# Audio.net
KiCad netlist of a schematic drawn in Altium Designer
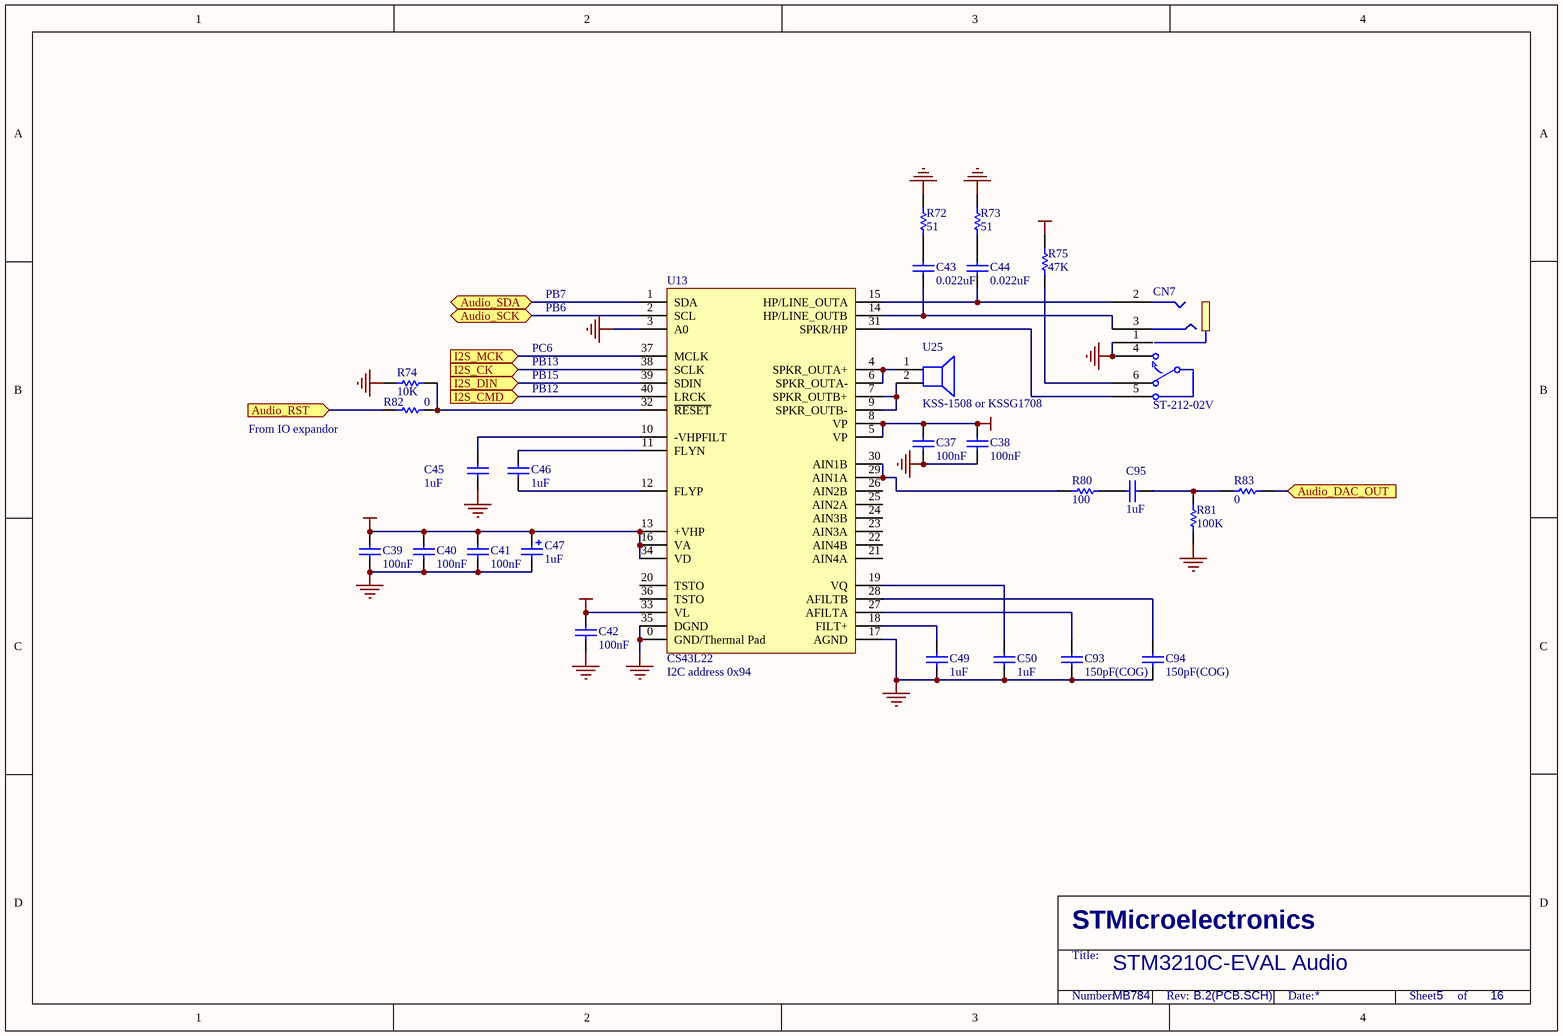
[diagram p0: Audio.SchDoc]

(export (version "E")
  (design (tool "Eeschema 10.0.6"))
  (components
    (comp (ref "C37")
      (value "100nF")
      (footprint "0603C")
      (description "Capacitor")
      (fields (field (name "PUBLISHER") "Altium Limited"))
      (libsource (lib "Miscellaneous Devices") (part "CAP"))
    )
    (comp (ref "C38")
      (value "100nF")
      (footprint "0603C")
      (description "Capacitor")
      (fields (field (name "PUBLISHER") "Altium Limited"))
      (libsource (lib "Miscellaneous Devices") (part "CAP"))
    )
    (comp (ref "C39")
      (value "100nF")
      (footprint "0603C")
      (description "Capacitor")
      (fields (field (name "PUBLISHER") "Altium Limited"))
      (libsource (lib "Miscellaneous Devices") (part "CAP"))
    )
    (comp (ref "C40")
      (value "100nF")
      (footprint "0603C")
      (description "Capacitor")
      (fields (field (name "PUBLISHER") "Altium Limited"))
      (libsource (lib "Miscellaneous Devices") (part "CAP"))
    )
    (comp (ref "C41")
      (value "100nF")
      (footprint "0603C")
      (description "Capacitor")
      (fields (field (name "PUBLISHER") "Altium Limited"))
      (libsource (lib "Miscellaneous Devices") (part "CAP"))
    )
    (comp (ref "C42")
      (value "100nF")
      (footprint "0603C")
      (description "Capacitor")
      (fields (field (name "PUBLISHER") "Altium Limited"))
      (libsource (lib "Miscellaneous Devices") (part "CAP"))
    )
    (comp (ref "C43")
      (value "0.022uF")
      (footprint "0603C")
      (description "Capacitor")
      (fields (field (name "PUBLISHER") "Altium Limited"))
      (libsource (lib "Miscellaneous Devices") (part "CAP"))
    )
    (comp (ref "C44")
      (value "0.022uF")
      (footprint "0603C")
      (description "Capacitor")
      (fields (field (name "PUBLISHER") "Altium Limited"))
      (libsource (lib "Miscellaneous Devices") (part "CAP"))
    )
    (comp (ref "C45")
      (value "1uF")
      (footprint "0603C")
      (description "Capacitor")
      (fields (field (name "PUBLISHER") "Altium Limited"))
      (libsource (lib "Miscellaneous Devices") (part "CAP"))
    )
    (comp (ref "C46")
      (value "1uF")
      (footprint "0603C")
      (description "Capacitor")
      (fields (field (name "PUBLISHER") "Altium Limited"))
      (libsource (lib "Miscellaneous Devices") (part "CAP"))
    )
    (comp (ref "C47")
      (value "1uF")
      (footprint "TAN-A")
      (description "Polarized Capacitor (Radial)")
      (fields (field (name "PUBLISHER") "Altium Limited"))
      (libsource (lib "Miscellaneous Devices") (part "Cap Pol1"))
    )
    (comp (ref "C49")
      (value "1uF")
      (footprint "0603C")
      (description "Capacitor")
      (fields (field (name "PUBLISHER") "Altium Limited"))
      (libsource (lib "Miscellaneous Devices") (part "CAP"))
    )
    (comp (ref "C50")
      (value "1uF")
      (footprint "0603C")
      (description "Capacitor")
      (fields (field (name "PUBLISHER") "Altium Limited"))
      (libsource (lib "Miscellaneous Devices") (part "CAP"))
    )
    (comp (ref "C93")
      (value "150pF(COG)")
      (footprint "0603C")
      (description "Capacitor")
      (fields (field (name "PUBLISHER") "Altium Limited"))
      (libsource (lib "Miscellaneous Devices") (part "CAP"))
    )
    (comp (ref "C94")
      (value "150pF(COG)")
      (footprint "0603C")
      (description "Capacitor")
      (fields (field (name "PUBLISHER") "Altium Limited"))
      (libsource (lib "Miscellaneous Devices") (part "CAP"))
    )
    (comp (ref "C95")
      (value "1uF")
      (footprint "0603C")
      (description "Capacitor")
      (fields (field (name "PUBLISHER") "Altium Limited"))
      (libsource (lib "Miscellaneous Devices") (part "CAP"))
    )
    (comp (ref "CN7")
      (value "ST-212-02V")
      (footprint "ST-212-02V")
      (libsource (lib "MB784") (part "ST-212-02V"))
    )
    (comp (ref "R72")
      (value "51")
      (footprint "0603R")
      (description "Resistor")
      (fields (field (name "PUBLISHER") "Altium Limited"))
      (libsource (lib "Miscellaneous Devices") (part "res1"))
    )
    (comp (ref "R73")
      (value "51")
      (footprint "0603R")
      (description "Resistor")
      (fields (field (name "PUBLISHER") "Altium Limited"))
      (libsource (lib "Miscellaneous Devices") (part "res1"))
    )
    (comp (ref "R74")
      (value "10K")
      (footprint "0603R")
      (description "Resistor")
      (fields (field (name "PUBLISHER") "Altium Limited"))
      (libsource (lib "Miscellaneous Devices") (part "res1"))
    )
    (comp (ref "R75")
      (value "47K")
      (footprint "0603R")
      (description "Resistor")
      (fields (field (name "PUBLISHER") "Altium Limited"))
      (libsource (lib "Miscellaneous Devices") (part "res1"))
    )
    (comp (ref "R80")
      (value "100")
      (footprint "0603R")
      (description "Resistor")
      (fields (field (name "PUBLISHER") "Altium Limited"))
      (libsource (lib "Miscellaneous Devices") (part "res1"))
    )
    (comp (ref "R81")
      (value "100K")
      (footprint "0603R")
      (description "Resistor")
      (fields (field (name "PUBLISHER") "Altium Limited"))
      (libsource (lib "Miscellaneous Devices") (part "res1"))
    )
    (comp (ref "R82")
      (value "0")
      (footprint "0603R")
      (description "Resistor")
      (fields (field (name "PUBLISHER") "Altium Limited"))
      (libsource (lib "Miscellaneous Devices") (part "res1"))
    )
    (comp (ref "R83")
      (value "0")
      (footprint "0603R")
      (description "Resistor")
      (fields (field (name "PUBLISHER") "Altium Limited"))
      (libsource (lib "Miscellaneous Devices") (part "res1"))
    )
    (comp (ref "U13") (value "CS43L22") (footprint "QFN40(6*6)") (libsource (lib "MB784") (part "CS43L22")))
    (comp (ref "U25")
      (value "KSS-1508 or KSSG1708")
      (footprint "KS1708")
      (description "Loudspeaker")
      (fields (field (name "PUBLISHER") "Altium Limited"))
      (libsource (lib "Miscellaneous Devices") (part "Speaker"))
    )
  )
  (nets
    (net (code "1") (name "+2V5") (class "Default")
      (node (ref "C39") (pin "2") (pinfunction "2_2") (pintype "passive"))
      (node (ref "C40") (pin "2") (pinfunction "2_2") (pintype "passive"))
      (node (ref "C41") (pin "2") (pinfunction "2_2") (pintype "passive"))
      (node (ref "C47") (pin "1") (pinfunction "1_1") (pintype "passive"))
      (node (ref "R75") (pin "1") (pinfunction "1_1") (pintype "passive"))
      (node (ref "U13") (pin "13") (pinfunction "+VHP_13") (pintype "passive"))
      (node (ref "U13") (pin "16") (pinfunction "VA_16") (pintype "passive"))
      (node (ref "U13") (pin "34") (pinfunction "VD_34") (pintype "passive"))
    )
    (net (code "2") (name "+3V3") (class "Default")
      (node (ref "C42") (pin "2") (pinfunction "2_2") (pintype "passive"))
      (node (ref "U13") (pin "33") (pinfunction "VL_33") (pintype "passive"))
    )
    (net (code "3") (name "+5V") (class "Default")
      (node (ref "C37") (pin "1") (pinfunction "1_1") (pintype "passive"))
      (node (ref "C38") (pin "1") (pinfunction "1_1") (pintype "passive"))
      (node (ref "U13") (pin "5") (pinfunction "VP_5") (pintype "passive"))
      (node (ref "U13") (pin "8") (pinfunction "VP_8") (pintype "passive"))
    )
    (net (code "4") (name "/Audio_DAC_OUT") (class "Default")
      (node (ref "R83") (pin "2") (pinfunction "2_2") (pintype "passive"))
    )
    (net (code "5") (name "/Audio_RST") (class "Default")
      (node (ref "R82") (pin "2") (pinfunction "2_2") (pintype "passive"))
    )
    (net (code "6") (name "/Audio_SCK") (class "Default")
      (node (ref "U13") (pin "2") (pinfunction "SCL_2") (pintype "passive"))
    )
    (net (code "7") (name "/Audio_SDA") (class "Default")
      (node (ref "U13") (pin "1") (pinfunction "SDA_1") (pintype "passive"))
    )
    (net (code "8") (name "/I2S_CK") (class "Default")
      (node (ref "U13") (pin "38") (pinfunction "SCLK_38") (pintype "passive"))
    )
    (net (code "9") (name "/I2S_CMD") (class "Default")
      (node (ref "U13") (pin "40") (pinfunction "LRCK_40") (pintype "passive"))
    )
    (net (code "10") (name "/I2S_DIN") (class "Default")
      (node (ref "U13") (pin "39") (pinfunction "SDIN_39") (pintype "passive"))
    )
    (net (code "11") (name "/I2S_MCK") (class "Default")
      (node (ref "U13") (pin "37") (pinfunction "MCLK_37") (pintype "passive"))
    )
    (net (code "12") (name "GND") (class "Default")
      (node (ref "C37") (pin "2") (pinfunction "2_2") (pintype "passive"))
      (node (ref "C38") (pin "2") (pinfunction "2_2") (pintype "passive"))
      (node (ref "C39") (pin "1") (pinfunction "1_1") (pintype "passive"))
      (node (ref "C40") (pin "1") (pinfunction "1_1") (pintype "passive"))
      (node (ref "C41") (pin "1") (pinfunction "1_1") (pintype "passive"))
      (node (ref "C42") (pin "1") (pinfunction "1_1") (pintype "passive"))
      (node (ref "C45") (pin "2") (pinfunction "2_2") (pintype "passive"))
      (node (ref "C47") (pin "2") (pinfunction "2_2") (pintype "passive"))
      (node (ref "C49") (pin "1") (pinfunction "1_1") (pintype "passive"))
      (node (ref "C50") (pin "1") (pinfunction "1_1") (pintype "passive"))
      (node (ref "C93") (pin "1") (pinfunction "1_1") (pintype "passive"))
      (node (ref "C94") (pin "1") (pinfunction "1_1") (pintype "passive"))
      (node (ref "CN7") (pin "1") (pintype "passive"))
      (node (ref "CN7") (pin "4") (pintype "passive"))
      (node (ref "R72") (pin "1") (pinfunction "1_1") (pintype "passive"))
      (node (ref "R73") (pin "1") (pinfunction "1_1") (pintype "passive"))
      (node (ref "R74") (pin "2") (pinfunction "2_2") (pintype "passive"))
      (node (ref "R81") (pin "2") (pinfunction "2_2") (pintype "passive"))
      (node (ref "U13") (pin "0") (pinfunction "GND/Thermal_Pad_0") (pintype "passive"))
      (node (ref "U13") (pin "17") (pinfunction "AGND_17") (pintype "passive"))
      (node (ref "U13") (pin "3") (pinfunction "A0_3") (pintype "passive"))
      (node (ref "U13") (pin "35") (pinfunction "DGND_35") (pintype "passive"))
    )
    (net (code "13") (name "Net-(C43-Pad1)") (class "Default")
      (node (ref "C43") (pin "1") (pinfunction "1_1") (pintype "passive"))
      (node (ref "R72") (pin "2") (pinfunction "2_2") (pintype "passive"))
    )
    (net (code "14") (name "Net-(C44-Pad1)") (class "Default")
      (node (ref "C44") (pin "1") (pinfunction "1_1") (pintype "passive"))
      (node (ref "R73") (pin "2") (pinfunction "2_2") (pintype "passive"))
    )
    (net (code "15") (name "Net-(C95-Pad1)") (class "Default")
      (node (ref "C95") (pin "1") (pinfunction "1_1") (pintype "passive"))
      (node (ref "R80") (pin "1") (pinfunction "1_1") (pintype "passive"))
    )
    (net (code "16") (name "Net-(C95-Pad2)") (class "Default")
      (node (ref "C95") (pin "2") (pinfunction "2_2") (pintype "passive"))
      (node (ref "R81") (pin "1") (pinfunction "1_1") (pintype "passive"))
      (node (ref "R83") (pin "1") (pinfunction "1_1") (pintype "passive"))
    )
    (net (code "17") (name "Net-(CN7-Pad6)") (class "Default")
      (node (ref "CN7") (pin "6") (pintype "passive"))
      (node (ref "R75") (pin "2") (pinfunction "2_2") (pintype "passive"))
    )
    (net (code "18") (name "Net-(U13--VHPFILT)") (class "Default")
      (node (ref "C45") (pin "1") (pinfunction "1_1") (pintype "passive"))
      (node (ref "U13") (pin "10") (pinfunction "-VHPFILT_10") (pintype "passive"))
    )
    (net (code "19") (name "Net-(U13-AFILTA)") (class "Default")
      (node (ref "C93") (pin "2") (pinfunction "2_2") (pintype "passive"))
      (node (ref "U13") (pin "27") (pinfunction "AFILTA_27") (pintype "passive"))
    )
    (net (code "20") (name "Net-(U13-AFILTB)") (class "Default")
      (node (ref "C94") (pin "2") (pinfunction "2_2") (pintype "passive"))
      (node (ref "U13") (pin "28") (pinfunction "AFILTB_28") (pintype "passive"))
    )
    (net (code "21") (name "Net-(U13-AIN1A)") (class "Default")
      (node (ref "R80") (pin "2") (pinfunction "2_2") (pintype "passive"))
      (node (ref "U13") (pin "29") (pinfunction "AIN1A_29") (pintype "passive"))
      (node (ref "U13") (pin "30") (pinfunction "AIN1B_30") (pintype "passive"))
    )
    (net (code "22") (name "Net-(U13-FILT+)") (class "Default")
      (node (ref "C49") (pin "2") (pinfunction "2_2") (pintype "passive"))
      (node (ref "U13") (pin "18") (pinfunction "FILT+_18") (pintype "passive"))
    )
    (net (code "23") (name "Net-(U13-FLYN)") (class "Default")
      (node (ref "C46") (pin "2") (pinfunction "2_2") (pintype "passive"))
      (node (ref "U13") (pin "11") (pinfunction "FLYN_11") (pintype "passive"))
    )
    (net (code "24") (name "Net-(U13-FLYP)") (class "Default")
      (node (ref "C46") (pin "1") (pinfunction "1_1") (pintype "passive"))
      (node (ref "U13") (pin "12") (pinfunction "FLYP_12") (pintype "passive"))
    )
    (net (code "25") (name "Net-(U13-HP{slash}LINE_OUTA)") (class "Default")
      (node (ref "C44") (pin "2") (pinfunction "2_2") (pintype "passive"))
      (node (ref "CN7") (pin "2") (pintype "passive"))
      (node (ref "U13") (pin "15") (pinfunction "HP/LINE_OUTA_15") (pintype "passive"))
    )
    (net (code "26") (name "Net-(U13-HP{slash}LINE_OUTB)") (class "Default")
      (node (ref "C43") (pin "2") (pinfunction "2_2") (pintype "passive"))
      (node (ref "CN7") (pin "3") (pintype "passive"))
      (node (ref "U13") (pin "14") (pinfunction "HP/LINE_OUTB_14") (pintype "passive"))
    )
    (net (code "27") (name "Net-(U13-SPKR_OUTA+)") (class "Default")
      (node (ref "U13") (pin "4") (pinfunction "SPKR_OUTA+_4") (pintype "passive"))
      (node (ref "U13") (pin "6") (pinfunction "SPKR_OUTA-_6") (pintype "passive"))
      (node (ref "U25") (pin "1") (pinfunction "+_1") (pintype "passive"))
    )
    (net (code "28") (name "Net-(U13-SPKR_OUTB+)") (class "Default")
      (node (ref "U13") (pin "7") (pinfunction "SPKR_OUTB+_7") (pintype "passive"))
      (node (ref "U13") (pin "9") (pinfunction "SPKR_OUTB-_9") (pintype "passive"))
      (node (ref "U25") (pin "2") (pinfunction "-_2") (pintype "passive"))
    )
    (net (code "29") (name "Net-(U13-SPKR{slash}HP)") (class "Default")
      (node (ref "CN7") (pin "5") (pintype "passive"))
      (node (ref "U13") (pin "31") (pinfunction "SPKR/HP_31") (pintype "passive"))
    )
    (net (code "30") (name "Net-(U13-VQ)") (class "Default")
      (node (ref "C50") (pin "2") (pinfunction "2_2") (pintype "passive"))
      (node (ref "U13") (pin "19") (pinfunction "VQ_19") (pintype "passive"))
    )
    (net (code "31") (name "Net-(U13-~{RESET})") (class "Default")
      (node (ref "R74") (pin "1") (pinfunction "1_1") (pintype "passive"))
      (node (ref "R82") (pin "1") (pinfunction "1_1") (pintype "passive"))
      (node (ref "U13") (pin "32") (pinfunction "~{RESET}_32") (pintype "passive"))
    )
    (net (code "32") (name "unconnected-(U13-AIN2A-Pad25)") (class "Default")
      (node (ref "U13") (pin "25") (pinfunction "AIN2A_25") (pintype "passive"))
    )
    (net (code "33") (name "unconnected-(U13-AIN2B-Pad26)") (class "Default")
      (node (ref "U13") (pin "26") (pinfunction "AIN2B_26") (pintype "passive"))
    )
    (net (code "34") (name "unconnected-(U13-AIN3A-Pad23)") (class "Default")
      (node (ref "U13") (pin "23") (pinfunction "AIN3A_23") (pintype "passive"))
    )
    (net (code "35") (name "unconnected-(U13-AIN3B-Pad24)") (class "Default")
      (node (ref "U13") (pin "24") (pinfunction "AIN3B_24") (pintype "passive"))
    )
    (net (code "36") (name "unconnected-(U13-AIN4A-Pad21)") (class "Default")
      (node (ref "U13") (pin "21") (pinfunction "AIN4A_21") (pintype "passive"))
    )
    (net (code "37") (name "unconnected-(U13-AIN4B-Pad22)") (class "Default")
      (node (ref "U13") (pin "22") (pinfunction "AIN4B_22") (pintype "passive"))
    )
    (net (code "38") (name "unconnected-(U13-TSTO-Pad20)") (class "Default")
      (node (ref "U13") (pin "20") (pinfunction "TSTO_20") (pintype "passive"))
    )
    (net (code "39") (name "unconnected-(U13-TSTO-Pad36)") (class "Default")
      (node (ref "U13") (pin "36") (pinfunction "TSTO_36") (pintype "passive"))
    )
  )
)
